# DCMotorDriver.net
KiCad netlist of a schematic drawn in Altium Designer
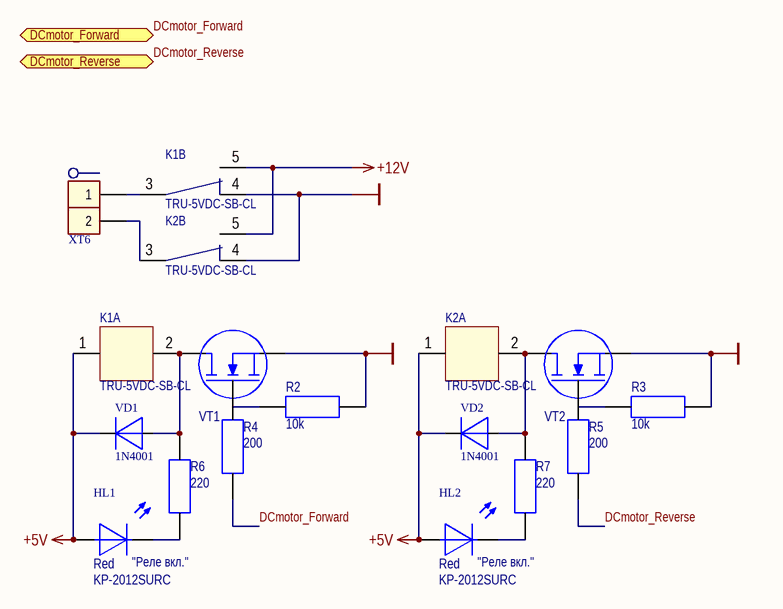
[diagram p0: DCMotorDriver.SchDoc]

(export (version "E")
  (design (tool "Eeschema 10.0.6"))
  (components
    (comp (ref "HL1")
      (value "Red")
      (footprint "Indicator:DIOMELF2012M")
      (description "Diod LED SMD Red")
      (fields (field (name "MANUFACTURERPARTNUMBER") "KP-2012SURC"))
      (libsource (lib "Indicator") (part "LED1_R"))
    )
    (comp (ref "HL2")
      (value "Red")
      (footprint "Indicator:DIOMELF2012M")
      (description "Diod LED SMD Red")
      (fields (field (name "MANUFACTURERPARTNUMBER") "KP-2012SURC"))
      (libsource (lib "Indicator") (part "LED1_R"))
    )
    (comp (ref "K1")
      (value "TRU-5VDC-SB-CL")
      (footprint "Switch:TRU-5VDC-SB-CL")
      (libsource (lib "Switch") (part "TRU-5VDC-SB-CL"))
    )
    (comp (ref "K2")
      (value "TRU-5VDC-SB-CL")
      (footprint "Switch:TRU-5VDC-SB-CL")
      (libsource (lib "Switch") (part "TRU-5VDC-SB-CL"))
    )
    (comp (ref "R2")
      (value "10k")
      (footprint "SMDRC0805")
      (description "Generic resistor")
      (fields (field (name "PARTNUMBER") "Resistor 0805 10k"))
      (libsource (lib "") (part "Resistor_1"))
    )
    (comp (ref "R3")
      (value "10k")
      (footprint "SMDRC0805")
      (description "Generic resistor")
      (fields (field (name "PARTNUMBER") "Resistor 0805 10k"))
      (libsource (lib "") (part "Resistor_1"))
    )
    (comp (ref "R4")
      (value "200")
      (footprint "SMDRC0805")
      (description "Generic resistor")
      (fields (field (name "PARTNUMBER") "Resistor 0805 200"))
      (libsource (lib "") (part "Resistor_2"))
    )
    (comp (ref "R5")
      (value "200")
      (footprint "SMDRC0805")
      (description "Generic resistor")
      (fields (field (name "PARTNUMBER") "Resistor 0805 200"))
      (libsource (lib "") (part "Resistor_2"))
    )
    (comp (ref "R6")
      (value "220")
      (footprint "SMDRC0805")
      (description "Generic resistor")
      (fields (field (name "PARTNUMBER") "Resistor 0805 220"))
      (libsource (lib "library") (part "Resistor"))
    )
    (comp (ref "R7")
      (value "220")
      (footprint "SMDRC0805")
      (description "Generic resistor")
      (fields (field (name "PARTNUMBER") "Resistor 0805 220"))
      (libsource (lib "library") (part "Resistor"))
    )
    (comp (ref "VD1")
      (value "1N4001")
      (footprint "DIod:PinDiode")
      (description "Rectifying diode")
      (fields (field (name "MANUFACTURERPARTNUMBER") "1N4001"))
      (libsource (lib "Diod") (part "1N4001"))
    )
    (comp (ref "VD2")
      (value "1N4001")
      (footprint "DIod:PinDiode")
      (description "Rectifying diode")
      (fields (field (name "MANUFACTURERPARTNUMBER") "1N4001"))
      (libsource (lib "Diod") (part "1N4001"))
    )
    (comp (ref "VT1")
      (value "2N7002")
      (footprint "Standard:SOT23 (TO-236AB)")
      (description "60V, 300mA N-channel Trench MOSFET")
      (libsource (lib "Transistor") (part "2N7002 n-MOSFET"))
    )
    (comp (ref "VT2")
      (value "2N7002")
      (footprint "Standard:SOT23 (TO-236AB)")
      (description "60V, 300mA N-channel Trench MOSFET")
      (libsource (lib "Transistor") (part "2N7002 n-MOSFET"))
    )
    (comp (ref "XT6")
      (value "330-021-12")
      (footprint "Connector:330-021-12")
      (description "Demountable connection  2-pin")
      (fields (field (name "MANUFACTURER") "Degson Electronics Co., Ltd"))
      (libsource (lib "Connector") (part "Con2_D 330-021-12"))
    )
  )
  (nets
    (net (code "1") (name "+5V") (class "Default")
      (node (ref "HL1") (pin "1") (pinfunction "1_1") (pintype "passive"))
      (node (ref "HL2") (pin "1") (pinfunction "1_1") (pintype "passive"))
      (node (ref "K1") (pin "1") (pinfunction "1_1") (pintype "passive"))
      (node (ref "K2") (pin "1") (pinfunction "1_1") (pintype "passive"))
      (node (ref "VD1") (pin "K") (pinfunction "K_K") (pintype "passive"))
      (node (ref "VD2") (pin "K") (pinfunction "K_K") (pintype "passive"))
    )
    (net (code "2") (name "+12V") (class "Default")
      (node (ref "K1") (pin "5") (pinfunction "5_5") (pintype "passive"))
      (node (ref "K2") (pin "5") (pinfunction "5_5") (pintype "passive"))
    )
    (net (code "3") (name "/DCmotor_Forward") (class "Default")
      (node (ref "R4") (pin "1") (pinfunction "1_1") (pintype "passive"))
    )
    (net (code "4") (name "/DCmotor_Reverse") (class "Default")
      (node (ref "R5") (pin "1") (pinfunction "1_1") (pintype "passive"))
    )
    (net (code "5") (name "GND") (class "Default")
      (node (ref "K1") (pin "4") (pinfunction "4_4") (pintype "passive"))
      (node (ref "K2") (pin "4") (pinfunction "4_4") (pintype "passive"))
      (node (ref "R2") (pin "2") (pinfunction "2_2") (pintype "passive"))
      (node (ref "R3") (pin "2") (pinfunction "2_2") (pintype "passive"))
      (node (ref "VT1") (pin "2") (pinfunction "S_2") (pintype "passive"))
      (node (ref "VT2") (pin "2") (pinfunction "S_2") (pintype "passive"))
    )
    (net (code "6") (name "Net-(HL1-Pad2)") (class "Default")
      (node (ref "HL1") (pin "2") (pinfunction "2_2") (pintype "passive"))
      (node (ref "R6") (pin "2") (pinfunction "2_2") (pintype "passive"))
    )
    (net (code "7") (name "Net-(HL2-Pad2)") (class "Default")
      (node (ref "HL2") (pin "2") (pinfunction "2_2") (pintype "passive"))
      (node (ref "R7") (pin "2") (pinfunction "2_2") (pintype "passive"))
    )
    (net (code "8") (name "Net-(K1-Pad3)") (class "Default")
      (node (ref "K1") (pin "3") (pinfunction "3_3") (pintype "passive"))
      (node (ref "XT6") (pin "1") (pinfunction "1_1") (pintype "passive"))
    )
    (net (code "9") (name "Net-(K2-Pad3)") (class "Default")
      (node (ref "K2") (pin "3") (pinfunction "3_3") (pintype "passive"))
      (node (ref "XT6") (pin "2") (pinfunction "2_2") (pintype "passive"))
    )
    (net (code "10") (name "Net-(VT1-D)") (class "Default")
      (node (ref "K1") (pin "2") (pinfunction "2_2") (pintype "passive"))
      (node (ref "R6") (pin "1") (pinfunction "1_1") (pintype "passive"))
      (node (ref "VD1") (pin "A") (pinfunction "A_A") (pintype "passive"))
      (node (ref "VT1") (pin "3") (pinfunction "D_3") (pintype "passive"))
    )
    (net (code "11") (name "Net-(VT1-G)") (class "Default")
      (node (ref "R2") (pin "1") (pinfunction "1_1") (pintype "passive"))
      (node (ref "VT1") (pin "1") (pinfunction "G_1") (pintype "passive"))
    )
    (net (code "12") (name "Net-(VT2-D)") (class "Default")
      (node (ref "K2") (pin "2") (pinfunction "2_2") (pintype "passive"))
      (node (ref "R7") (pin "1") (pinfunction "1_1") (pintype "passive"))
      (node (ref "VD2") (pin "A") (pinfunction "A_A") (pintype "passive"))
      (node (ref "VT2") (pin "3") (pinfunction "D_3") (pintype "passive"))
    )
    (net (code "13") (name "Net-(VT2-G)") (class "Default")
      (node (ref "R3") (pin "1") (pinfunction "1_1") (pintype "passive"))
      (node (ref "VT2") (pin "1") (pinfunction "G_1") (pintype "passive"))
    )
    (net (code "14") (name "unconnected-(R4-Pad2)") (class "Default")
      (node (ref "R4") (pin "2") (pinfunction "2_2") (pintype "passive"))
    )
    (net (code "15") (name "unconnected-(R5-Pad2)") (class "Default")
      (node (ref "R5") (pin "2") (pinfunction "2_2") (pintype "passive"))
    )
  )
)
